# BSPD_rev10.net
KiCad netlist of a schematic drawn in EAGLE
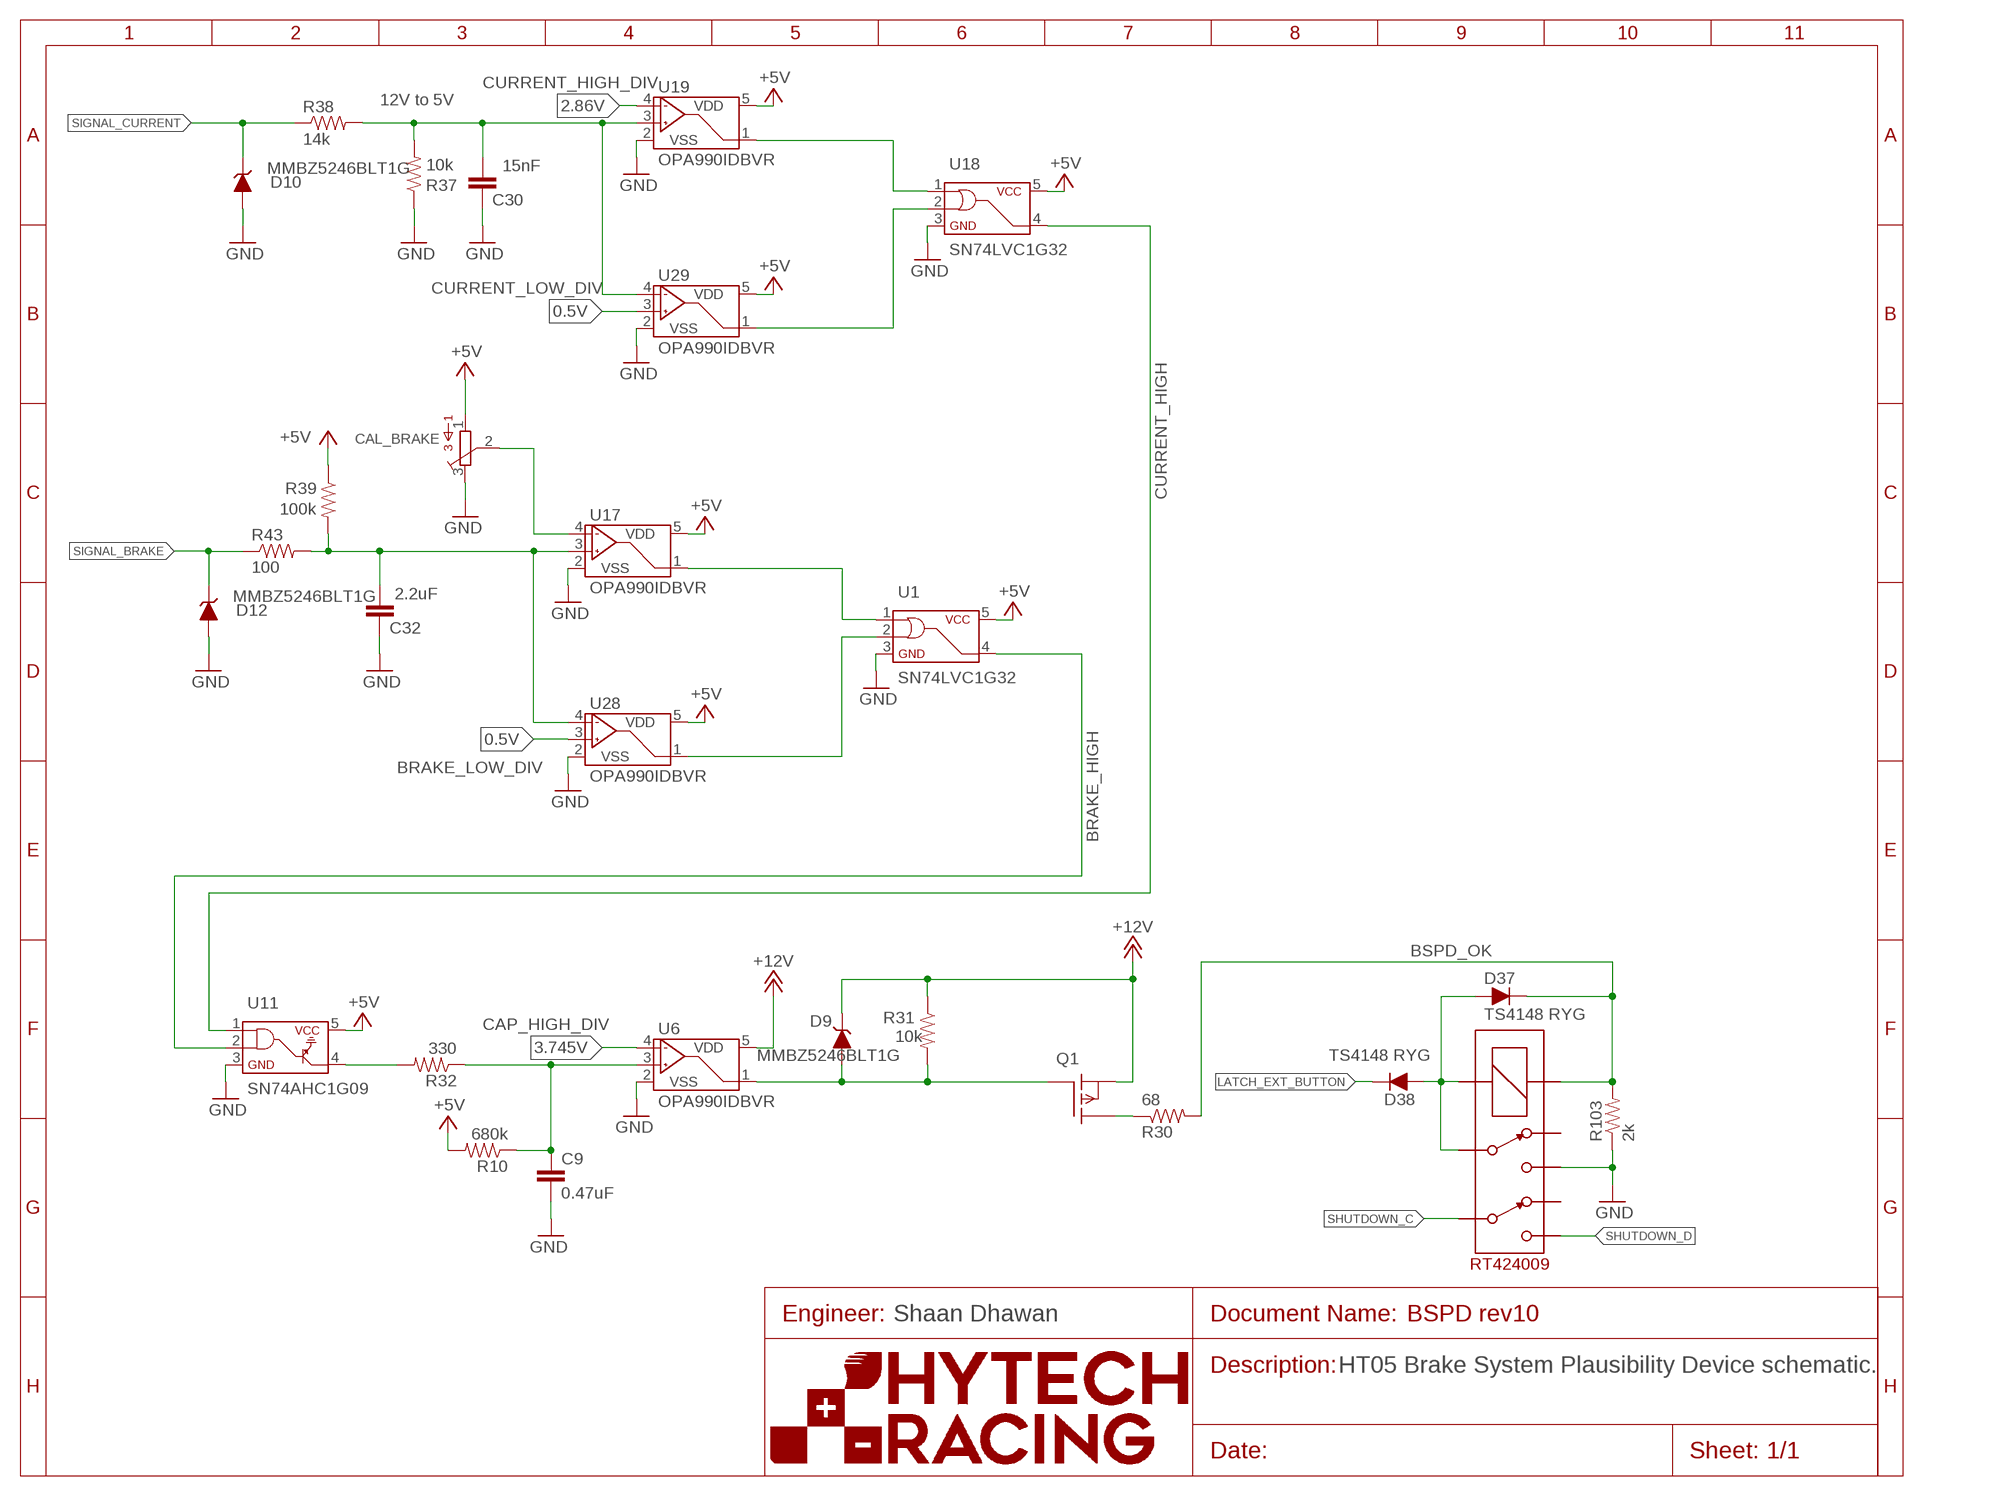
[diagram p0: schematic, sheet 1]

(export (version "E")
  (design (tool "Eeschema 10.0.6"))
  (components
    (comp (ref "C9")
      (value "0.47uF")
      (footprint "eagle-import:0603-CAP")
      (libsource (lib "eagle-import") (part "CAP0603-CAP"))
    )
    (comp (ref "C30")
      (value "15nF")
      (footprint "eagle-import:0603-CAP")
      (libsource (lib "eagle-import") (part "CAP0603-CAP"))
    )
    (comp (ref "C32")
      (value "2.2uF")
      (footprint "eagle-import:0603-CAP")
      (libsource (lib "eagle-import") (part "CAP0603-CAP"))
    )
    (comp (ref "CAL_BRAKE")
      (value "TRIMPOT_3296C")
      (footprint "eagle-import:TRIMPOT_3296")
      (libsource (lib "eagle-import") (part "TRIMPOT_3296C"))
    )
    (comp (ref "D9")
      (value "MMBZ5246BLT1G")
      (footprint "eagle-import:SOT23")
      (libsource (lib "eagle-import") (part "DIODE_ZENER"))
    )
    (comp (ref "D10")
      (value "MMBZ5246BLT1G")
      (footprint "eagle-import:SOT23")
      (libsource (lib "eagle-import") (part "DIODE_ZENER"))
    )
    (comp (ref "D12")
      (value "MMBZ5246BLT1G")
      (footprint "eagle-import:SOT23")
      (libsource (lib "eagle-import") (part "DIODE_ZENER"))
    )
    (comp (ref "D37")
      (value "TS4148 RYG")
      (footprint "eagle-import:0805_D")
      (libsource (lib "eagle-import") (part "DIODE0805"))
    )
    (comp (ref "D38")
      (value "TS4148 RYG")
      (footprint "eagle-import:0805_D")
      (libsource (lib "eagle-import") (part "DIODE0805"))
    )
    (comp (ref "Q1")
      (value "P-CHANNEL_MOSFET_DMP3099L-7")
      (footprint "eagle-import:SOT23")
      (libsource (lib "eagle-import") (part "P-CHANNEL_MOSFET_DMP3099L-7"))
    )
    (comp (ref "R10")
      (value "680k")
      (footprint "eagle-import:0603-RES")
      (libsource (lib "eagle-import") (part "RESISTOR0603"))
    )
    (comp (ref "R30")
      (value "68")
      (footprint "eagle-import:0603-RES")
      (libsource (lib "eagle-import") (part "RESISTOR0603"))
    )
    (comp (ref "R31")
      (value "10k")
      (footprint "eagle-import:0603-RES")
      (libsource (lib "eagle-import") (part "RESISTOR0603"))
    )
    (comp (ref "R32")
      (value "330")
      (footprint "eagle-import:0603-RES")
      (libsource (lib "eagle-import") (part "RESISTOR0603"))
    )
    (comp (ref "R37")
      (value "10k")
      (footprint "eagle-import:0603-RES")
      (libsource (lib "eagle-import") (part "RESISTOR0603"))
    )
    (comp (ref "R38")
      (value "14k")
      (footprint "eagle-import:0603-RES")
      (libsource (lib "eagle-import") (part "RESISTOR0603"))
    )
    (comp (ref "R39")
      (value "100k")
      (footprint "eagle-import:0603-RES")
      (libsource (lib "eagle-import") (part "RESISTOR0603"))
    )
    (comp (ref "R43")
      (value "100")
      (footprint "eagle-import:0603-RES")
      (libsource (lib "eagle-import") (part "RESISTOR0603"))
    )
    (comp (ref "R103")
      (value "2k")
      (footprint "eagle-import:0603-RES")
      (libsource (lib "eagle-import") (part "RESISTOR0603"))
    )
    (comp (ref "U$37")
      (value "RT424009")
      (footprint "eagle-import:RELAY_DPDT")
      (libsource (lib "eagle-import") (part "RT424009"))
    )
    (comp (ref "U1")
      (value "SN74LVC1G32")
      (footprint "eagle-import:SOT-23-5")
      (libsource (lib "eagle-import") (part "SN74LVC1G32{dblquote}"))
    )
    (comp (ref "U6")
      (value "OPA990IDBVR")
      (footprint "eagle-import:SOT-23-5@1")
      (libsource (lib "eagle-import") (part "OPA990IDBVR"))
    )
    (comp (ref "U11")
      (value "SN74AHC1G09")
      (footprint "eagle-import:SOT-23-5")
      (libsource (lib "eagle-import") (part "SN74AHC1G09"))
    )
    (comp (ref "U17")
      (value "OPA990IDBVR")
      (footprint "eagle-import:SOT-23-5@1")
      (libsource (lib "eagle-import") (part "OPA990IDBVR"))
    )
    (comp (ref "U18")
      (value "SN74LVC1G32")
      (footprint "eagle-import:SOT-23-5")
      (libsource (lib "eagle-import") (part "SN74LVC1G32{dblquote}"))
    )
    (comp (ref "U19")
      (value "OPA990IDBVR")
      (footprint "eagle-import:SOT-23-5@1")
      (libsource (lib "eagle-import") (part "OPA990IDBVR"))
    )
    (comp (ref "U28")
      (value "OPA990IDBVR")
      (footprint "eagle-import:SOT-23-5@1")
      (libsource (lib "eagle-import") (part "OPA990IDBVR"))
    )
    (comp (ref "U29")
      (value "OPA990IDBVR")
      (footprint "eagle-import:SOT-23-5@1")
      (libsource (lib "eagle-import") (part "OPA990IDBVR"))
    )
  )
  (nets
    (net (code "1") (name "+5V") (class "Default")
      (node (ref "CAL_BRAKE") (pin "1") (pinfunction "1_1") (pintype "passive"))
      (node (ref "R10") (pin "2") (pinfunction "2_2") (pintype "passive"))
      (node (ref "R39") (pin "1") (pinfunction "1_1") (pintype "passive"))
      (node (ref "U1") (pin "5") (pinfunction "VCC_5") (pintype "passive"))
      (node (ref "U11") (pin "5") (pinfunction "5_5") (pintype "passive"))
      (node (ref "U17") (pin "5") (pinfunction "VDD_5") (pintype "passive"))
      (node (ref "U18") (pin "5") (pinfunction "VCC_5") (pintype "passive"))
      (node (ref "U19") (pin "5") (pinfunction "VDD_5") (pintype "passive"))
      (node (ref "U28") (pin "5") (pinfunction "VDD_5") (pintype "passive"))
      (node (ref "U29") (pin "5") (pinfunction "VDD_5") (pintype "passive"))
    )
    (net (code "2") (name "+12V") (class "Default")
      (node (ref "D9") (pin "3") (pinfunction "C_3") (pintype "passive"))
      (node (ref "Q1") (pin "2") (pinfunction "S_2") (pintype "passive"))
      (node (ref "R31") (pin "1") (pinfunction "1_1") (pintype "passive"))
      (node (ref "U6") (pin "5") (pinfunction "VDD_5") (pintype "passive"))
    )
    (net (code "3") (name "/BRAKE_HIGH") (class "Default")
      (node (ref "U1") (pin "4") (pinfunction "Y_4") (pintype "passive"))
      (node (ref "U11") (pin "2") (pinfunction "2_2") (pintype "passive"))
    )
    (net (code "4") (name "/BSPD_OK") (class "Default")
      (node (ref "D37") (pin "C") (pinfunction "C_C") (pintype "passive"))
      (node (ref "R103") (pin "2") (pinfunction "2_2") (pintype "passive"))
      (node (ref "R30") (pin "2") (pinfunction "2_2") (pintype "passive"))
      (node (ref "U$37") (pin "COIL+") (pinfunction "COIL+_COIL+") (pintype "bidirectional"))
    )
    (net (code "5") (name "/CURRENT_HIGH") (class "Default")
      (node (ref "U11") (pin "1") (pinfunction "1_1") (pintype "passive"))
      (node (ref "U18") (pin "4") (pinfunction "Y_4") (pintype "passive"))
    )
    (net (code "6") (name "0.5V") (class "Default")
      (node (ref "U28") (pin "3") (pinfunction "VIN+_3") (pintype "passive"))
      (node (ref "U29") (pin "3") (pinfunction "VIN+_3") (pintype "passive"))
    )
    (net (code "7") (name "2.86V") (class "Default")
      (node (ref "U19") (pin "4") (pinfunction "VIN-_4") (pintype "passive"))
    )
    (net (code "8") (name "3.745V") (class "Default")
      (node (ref "U6") (pin "4") (pinfunction "VIN-_4") (pintype "passive"))
    )
    (net (code "9") (name "GND") (class "Default")
      (node (ref "C30") (pin "1") (pinfunction "1_1") (pintype "passive"))
      (node (ref "C32") (pin "1") (pinfunction "1_1") (pintype "passive"))
      (node (ref "C9") (pin "2") (pinfunction "2_2") (pintype "passive"))
      (node (ref "CAL_BRAKE") (pin "3") (pinfunction "3_3") (pintype "passive"))
      (node (ref "D10") (pin "1") (pinfunction "A_1") (pintype "passive"))
      (node (ref "D12") (pin "1") (pinfunction "A_1") (pintype "passive"))
      (node (ref "R103") (pin "1") (pinfunction "1_1") (pintype "passive"))
      (node (ref "R37") (pin "1") (pinfunction "1_1") (pintype "passive"))
      (node (ref "U$37") (pin "4") (pinfunction "4_4") (pintype "bidirectional"))
      (node (ref "U1") (pin "3") (pinfunction "GND_3") (pintype "passive"))
      (node (ref "U11") (pin "3") (pinfunction "3_3") (pintype "passive"))
      (node (ref "U17") (pin "2") (pinfunction "VSS_2") (pintype "passive"))
      (node (ref "U18") (pin "3") (pinfunction "GND_3") (pintype "passive"))
      (node (ref "U19") (pin "2") (pinfunction "VSS_2") (pintype "passive"))
      (node (ref "U28") (pin "2") (pinfunction "VSS_2") (pintype "passive"))
      (node (ref "U29") (pin "2") (pinfunction "VSS_2") (pintype "passive"))
      (node (ref "U6") (pin "2") (pinfunction "VSS_2") (pintype "passive"))
    )
    (net (code "10") (name "LATCH_EXT_BUTTON") (class "Default")
      (node (ref "D38") (pin "C") (pinfunction "C_C") (pintype "passive"))
    )
    (net (code "11") (name "Net-(D9-A)") (class "Default")
      (node (ref "D9") (pin "1") (pinfunction "A_1") (pintype "passive"))
      (node (ref "Q1") (pin "1") (pinfunction "G_1") (pintype "passive"))
      (node (ref "R31") (pin "2") (pinfunction "2_2") (pintype "passive"))
      (node (ref "U6") (pin "1") (pinfunction "VOUT_1") (pintype "passive"))
    )
    (net (code "12") (name "Net-(D37-PadA)") (class "Default")
      (node (ref "D37") (pin "A") (pinfunction "A_A") (pintype "passive"))
      (node (ref "D38") (pin "A") (pinfunction "A_A") (pintype "passive"))
      (node (ref "U$37") (pin "3") (pinfunction "3_3") (pintype "bidirectional"))
      (node (ref "U$37") (pin "COIL-") (pinfunction "COIL-_COIL-") (pintype "bidirectional"))
    )
    (net (code "13") (name "Net-(Q1-D)") (class "Default")
      (node (ref "Q1") (pin "3") (pinfunction "D_3") (pintype "passive"))
      (node (ref "R30") (pin "1") (pinfunction "1_1") (pintype "passive"))
    )
    (net (code "14") (name "Net-(R32-Pad2)") (class "Default")
      (node (ref "R32") (pin "2") (pinfunction "2_2") (pintype "passive"))
      (node (ref "U11") (pin "4") (pinfunction "4_4") (pintype "passive"))
    )
    (net (code "15") (name "Net-(U1-A)") (class "Default")
      (node (ref "U1") (pin "1") (pinfunction "A_1") (pintype "passive"))
      (node (ref "U17") (pin "1") (pinfunction "VOUT_1") (pintype "passive"))
    )
    (net (code "16") (name "Net-(U1-B)") (class "Default")
      (node (ref "U1") (pin "2") (pinfunction "B_2") (pintype "passive"))
      (node (ref "U28") (pin "1") (pinfunction "VOUT_1") (pintype "passive"))
    )
    (net (code "17") (name "Net-(U6-VIN+)") (class "Default")
      (node (ref "C9") (pin "1") (pinfunction "1_1") (pintype "passive"))
      (node (ref "R10") (pin "1") (pinfunction "1_1") (pintype "passive"))
      (node (ref "R32") (pin "1") (pinfunction "1_1") (pintype "passive"))
      (node (ref "U6") (pin "3") (pinfunction "VIN+_3") (pintype "passive"))
    )
    (net (code "18") (name "Net-(U17-VIN+)") (class "Default")
      (node (ref "C32") (pin "2") (pinfunction "2_2") (pintype "passive"))
      (node (ref "R39") (pin "2") (pinfunction "2_2") (pintype "passive"))
      (node (ref "R43") (pin "2") (pinfunction "2_2") (pintype "passive"))
      (node (ref "U17") (pin "3") (pinfunction "VIN+_3") (pintype "passive"))
      (node (ref "U28") (pin "4") (pinfunction "VIN-_4") (pintype "passive"))
    )
    (net (code "19") (name "Net-(U17-VIN-)") (class "Default")
      (node (ref "CAL_BRAKE") (pin "2") (pinfunction "2_2") (pintype "passive"))
      (node (ref "U17") (pin "4") (pinfunction "VIN-_4") (pintype "passive"))
    )
    (net (code "20") (name "Net-(U18-A)") (class "Default")
      (node (ref "U18") (pin "1") (pinfunction "A_1") (pintype "passive"))
      (node (ref "U19") (pin "1") (pinfunction "VOUT_1") (pintype "passive"))
    )
    (net (code "21") (name "Net-(U18-B)") (class "Default")
      (node (ref "U18") (pin "2") (pinfunction "B_2") (pintype "passive"))
      (node (ref "U29") (pin "1") (pinfunction "VOUT_1") (pintype "passive"))
    )
    (net (code "22") (name "Net-(U19-VIN+)") (class "Default")
      (node (ref "C30") (pin "2") (pinfunction "2_2") (pintype "passive"))
      (node (ref "R37") (pin "2") (pinfunction "2_2") (pintype "passive"))
      (node (ref "R38") (pin "2") (pinfunction "2_2") (pintype "passive"))
      (node (ref "U19") (pin "3") (pinfunction "VIN+_3") (pintype "passive"))
      (node (ref "U29") (pin "4") (pinfunction "VIN-_4") (pintype "passive"))
    )
    (net (code "23") (name "SHUTDOWN_C") (class "Default")
      (node (ref "U$37") (pin "6") (pinfunction "6_6") (pintype "bidirectional"))
    )
    (net (code "24") (name "SHUTDOWN_D") (class "Default")
      (node (ref "U$37") (pin "5") (pinfunction "5_5") (pintype "bidirectional"))
    )
    (net (code "25") (name "SIGNAL_BRAKE") (class "Default")
      (node (ref "D12") (pin "3") (pinfunction "C_3") (pintype "passive"))
      (node (ref "R43") (pin "1") (pinfunction "1_1") (pintype "passive"))
    )
    (net (code "26") (name "SIGNAL_CURRENT") (class "Default")
      (node (ref "D10") (pin "3") (pinfunction "C_3") (pintype "passive"))
      (node (ref "R38") (pin "1") (pinfunction "1_1") (pintype "passive"))
    )
    (net (code "27") (name "unconnected-(U$37-Pad2)") (class "Default")
      (node (ref "U$37") (pin "2") (pinfunction "2_2") (pintype "bidirectional"))
    )
    (net (code "28") (name "unconnected-(U$37-Pad7)") (class "Default")
      (node (ref "U$37") (pin "7") (pinfunction "7_7") (pintype "bidirectional"))
    )
  )
)
